# wesleyremote.net
KiCad netlist of a schematic drawn in EAGLE
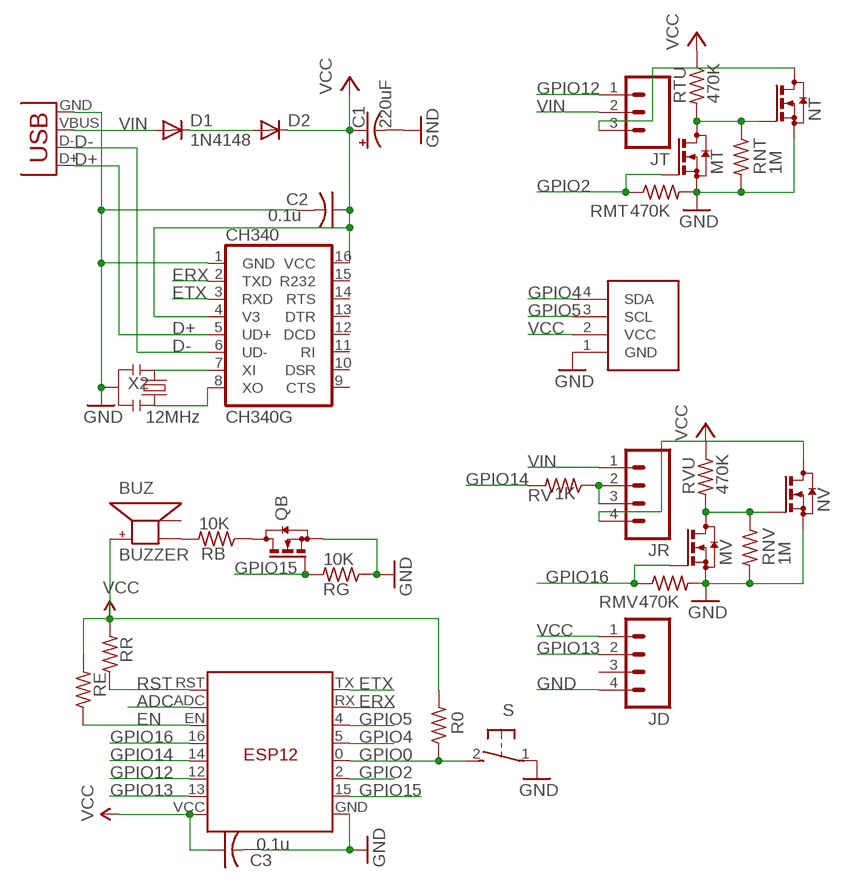
[diagram p0: schematic, sheet 1]

(export (version "E")
  (design (tool "Eeschema 10.0.6"))
  (components
    (comp (ref "BUZ")
      (value "BUZZER")
      (footprint "eagle-import:SMT-8585-BUZZER")
      (libsource (lib "eagle-import") (part "BUZZER"))
    )
    (comp (ref "C1")
      (value "220uF")
      (footprint "eagle-import:EIA3528-KIT")
      (libsource (lib "eagle-import") (part "CAP_POL3528-KIT"))
    )
    (comp (ref "C2")
      (value "0.1u")
      (footprint "eagle-import:C0603K")
      (libsource (lib "eagle-import") (part "C-USC0603K"))
    )
    (comp (ref "C3")
      (value "0.1u")
      (footprint "eagle-import:C0603K")
      (libsource (lib "eagle-import") (part "C-USC0603K"))
    )
    (comp (ref "CH340")
      (value "CH340G")
      (footprint "eagle-import:SO16")
      (libsource (lib "eagle-import") (part "CH340G"))
    )
    (comp (ref "D1")
      (value "1N4148")
      (footprint "eagle-import:MINIMELF")
      (libsource (lib "eagle-import") (part "DIODE-MINIMELF"))
    )
    (comp (ref "D2")
      (value "DIODE-MINIMELF")
      (footprint "eagle-import:MINIMELF")
      (libsource (lib "eagle-import") (part "DIODE-MINIMELF"))
    )
    (comp (ref "ESP12")
      (value "ESP12ESPWES")
      (footprint "eagle-import:ESP12_WES")
      (libsource (lib "eagle-import") (part "ESP12ESPWES"))
    )
    (comp (ref "JD")
      (value "M04DHT")
      (footprint "eagle-import:1X04_DHT_RFRX")
      (libsource (lib "eagle-import") (part "M04DHT"))
    )
    (comp (ref "JR")
      (value "M04RFRX")
      (footprint "eagle-import:1X04_RFRX")
      (libsource (lib "eagle-import") (part "M04RFRX"))
    )
    (comp (ref "JT")
      (value "M03RFTX")
      (footprint "eagle-import:1X03_RFTX")
      (libsource (lib "eagle-import") (part "M03RFTX"))
    )
    (comp (ref "MT")
      (value "AO3400")
      (footprint "eagle-import:SOT23")
      (libsource (lib "eagle-import") (part "BSS123"))
    )
    (comp (ref "MV")
      (value "AO3400")
      (footprint "eagle-import:SOT23")
      (libsource (lib "eagle-import") (part "BSS123"))
    )
    (comp (ref "NT")
      (value "AO3400")
      (footprint "eagle-import:SOT23")
      (libsource (lib "eagle-import") (part "BSS123"))
    )
    (comp (ref "NV")
      (value "AO3400")
      (footprint "eagle-import:SOT23")
      (libsource (lib "eagle-import") (part "BSS123"))
    )
    (comp (ref "QB")
      (value "AO3400")
      (footprint "eagle-import:SOT23")
      (libsource (lib "eagle-import") (part "BSS123"))
    )
    (comp (ref "R0")
      (value "R-US_R0603")
      (footprint "eagle-import:R0603")
      (libsource (lib "eagle-import") (part "R-US_R0603"))
    )
    (comp (ref "RB")
      (value "10K")
      (footprint "eagle-import:R0603")
      (libsource (lib "eagle-import") (part "adafruit2013_R-US_R0603"))
    )
    (comp (ref "RE")
      (value "R-US_R0603")
      (footprint "eagle-import:R0603")
      (libsource (lib "eagle-import") (part "R-US_R0603"))
    )
    (comp (ref "RG")
      (value "10K")
      (footprint "eagle-import:R0603")
      (libsource (lib "eagle-import") (part "adafruit2013_R-US_R0603"))
    )
    (comp (ref "RMT")
      (value "470K")
      (footprint "eagle-import:R0603")
      (libsource (lib "eagle-import") (part "R-US_R0603"))
    )
    (comp (ref "RMV")
      (value "470K")
      (footprint "eagle-import:R0603")
      (libsource (lib "eagle-import") (part "R-US_R0603"))
    )
    (comp (ref "RNT")
      (value "1M")
      (footprint "eagle-import:R0603")
      (libsource (lib "eagle-import") (part "R-US_R0603"))
    )
    (comp (ref "RNV")
      (value "1M")
      (footprint "eagle-import:R0603")
      (libsource (lib "eagle-import") (part "R-US_R0603"))
    )
    (comp (ref "RR")
      (value "R-US_R0603")
      (footprint "eagle-import:R0603")
      (libsource (lib "eagle-import") (part "R-US_R0603"))
    )
    (comp (ref "RTU")
      (value "470K")
      (footprint "eagle-import:R0603")
      (libsource (lib "eagle-import") (part "R-US_R0603"))
    )
    (comp (ref "RV")
      (value "1K")
      (footprint "eagle-import:R0603")
      (libsource (lib "eagle-import") (part "R-US_R0603"))
    )
    (comp (ref "RVU")
      (value "470K")
      (footprint "eagle-import:R0603")
      (libsource (lib "eagle-import") (part "R-US_R0603"))
    )
    (comp (ref "S")
      (value "31-XX")
      (footprint "eagle-import:B3F-31XX")
      (libsource (lib "eagle-import") (part "31-XX"))
    )
    (comp (ref "U$1")
      (value "SSD1306_OLED_I2C")
      (footprint "eagle-import:SSD1306_OLED_I2C")
      (libsource (lib "eagle-import") (part "SSD1306_OLED_I2C"))
    )
    (comp (ref "X2")
      (value "12MHz")
      (footprint "eagle-import:RESONATOR-SMD")
      (libsource (lib "eagle-import") (part "RESONATORSMD"))
    )
    (comp (ref "X3")
      (value "USBMICROB2")
      (footprint "eagle-import:USB-MICROB2")
      (libsource (lib "eagle-import") (part "USBMICROB2"))
    )
  )
  (nets
    (net (code "1") (name "/ADC") (class "Default")
      (node (ref "ESP12") (pin "ADC") (pinfunction "ADC_ADC") (pintype "bidirectional"))
    )
    (net (code "2") (name "/D+") (class "Default")
      (node (ref "CH340") (pin "5") (pinfunction "UD+_5") (pintype "bidirectional"))
      (node (ref "X3") (pin "D+") (pinfunction "D+_D+") (pintype "bidirectional"))
    )
    (net (code "3") (name "/D-") (class "Default")
      (node (ref "CH340") (pin "6") (pinfunction "UD-_6") (pintype "bidirectional"))
      (node (ref "X3") (pin "D-") (pinfunction "D-_D-") (pintype "bidirectional"))
    )
    (net (code "4") (name "/EN") (class "Default")
      (node (ref "ESP12") (pin "EN") (pinfunction "EN_EN") (pintype "bidirectional"))
      (node (ref "RE") (pin "1") (pinfunction "1_1") (pintype "passive"))
    )
    (net (code "5") (name "/ERX") (class "Default")
      (node (ref "CH340") (pin "2") (pinfunction "TXD_2") (pintype "bidirectional"))
      (node (ref "ESP12") (pin "RX") (pinfunction "RX_RX") (pintype "bidirectional"))
    )
    (net (code "6") (name "/ETX") (class "Default")
      (node (ref "CH340") (pin "3") (pinfunction "RXD_3") (pintype "bidirectional"))
      (node (ref "ESP12") (pin "TX") (pinfunction "TX_TX") (pintype "bidirectional"))
    )
    (net (code "7") (name "/GPIO0") (class "Default")
      (node (ref "ESP12") (pin "0") (pinfunction "G0_0") (pintype "bidirectional"))
      (node (ref "R0") (pin "1") (pinfunction "1_1") (pintype "passive"))
      (node (ref "S") (pin "2") (pinfunction "S_2") (pintype "passive"))
    )
    (net (code "8") (name "/GPIO2") (class "Default")
      (node (ref "ESP12") (pin "2") (pinfunction "G2_2") (pintype "bidirectional"))
      (node (ref "MT") (pin "1") (pinfunction "G_1") (pintype "passive"))
      (node (ref "RMT") (pin "1") (pinfunction "1_1") (pintype "passive"))
    )
    (net (code "9") (name "/GPIO4") (class "Default")
      (node (ref "ESP12") (pin "5") (pinfunction "G5_5") (pintype "bidirectional"))
      (node (ref "U$1") (pin "4") (pinfunction "SDA_4") (pintype "bidirectional"))
    )
    (net (code "10") (name "/GPIO5") (class "Default")
      (node (ref "ESP12") (pin "4") (pinfunction "G4_4") (pintype "bidirectional"))
      (node (ref "U$1") (pin "3") (pinfunction "SCL_3") (pintype "bidirectional"))
    )
    (net (code "11") (name "/GPIO12") (class "Default")
      (node (ref "ESP12") (pin "12") (pinfunction "G12_12") (pintype "bidirectional"))
      (node (ref "JT") (pin "1") (pinfunction "1_1") (pintype "passive"))
    )
    (net (code "12") (name "/GPIO13") (class "Default")
      (node (ref "ESP12") (pin "13") (pinfunction "G13_13") (pintype "bidirectional"))
      (node (ref "JD") (pin "2") (pinfunction "2_2") (pintype "passive"))
    )
    (net (code "13") (name "/GPIO14") (class "Default")
      (node (ref "ESP12") (pin "14") (pinfunction "G14_14") (pintype "bidirectional"))
      (node (ref "RV") (pin "2") (pinfunction "2_2") (pintype "passive"))
    )
    (net (code "14") (name "/GPIO15") (class "Default")
      (node (ref "ESP12") (pin "15") (pinfunction "G15_15") (pintype "bidirectional"))
      (node (ref "QB") (pin "1") (pinfunction "G_1") (pintype "passive"))
      (node (ref "RG") (pin "2") (pinfunction "2_2") (pintype "passive"))
    )
    (net (code "15") (name "/GPIO16") (class "Default")
      (node (ref "ESP12") (pin "16") (pinfunction "G16_16") (pintype "bidirectional"))
      (node (ref "MV") (pin "1") (pinfunction "G_1") (pintype "passive"))
      (node (ref "RMV") (pin "1") (pinfunction "1_1") (pintype "passive"))
    )
    (net (code "16") (name "/RST") (class "Default")
      (node (ref "ESP12") (pin "RST") (pinfunction "RST_RST") (pintype "bidirectional"))
      (node (ref "RR") (pin "1") (pinfunction "1_1") (pintype "passive"))
    )
    (net (code "17") (name "/VIN") (class "Default")
      (node (ref "D1") (pin "A") (pinfunction "A_A") (pintype "passive"))
      (node (ref "JR") (pin "1") (pinfunction "1_1") (pintype "passive"))
      (node (ref "JT") (pin "2") (pinfunction "2_2") (pintype "passive"))
      (node (ref "X3") (pin "VBUS") (pinfunction "VBUS_VBUS") (pintype "bidirectional"))
    )
    (net (code "18") (name "GND") (class "Default")
      (node (ref "C1") (pin "C") (pinfunction "-_C") (pintype "passive"))
      (node (ref "C2") (pin "2") (pinfunction "2_2") (pintype "passive"))
      (node (ref "C3") (pin "2") (pinfunction "2_2") (pintype "passive"))
      (node (ref "CH340") (pin "1") (pinfunction "GND_1") (pintype "power_in"))
      (node (ref "ESP12") (pin "GND") (pinfunction "GND_GND") (pintype "power_in"))
      (node (ref "JD") (pin "4") (pinfunction "4_4") (pintype "passive"))
      (node (ref "MT") (pin "2") (pinfunction "S_2") (pintype "passive"))
      (node (ref "MV") (pin "2") (pinfunction "S_2") (pintype "passive"))
      (node (ref "NT") (pin "2") (pinfunction "S_2") (pintype "passive"))
      (node (ref "NV") (pin "2") (pinfunction "S_2") (pintype "passive"))
      (node (ref "QB") (pin "2") (pinfunction "S_2") (pintype "passive"))
      (node (ref "RG") (pin "1") (pinfunction "1_1") (pintype "passive"))
      (node (ref "RMT") (pin "2") (pinfunction "2_2") (pintype "passive"))
      (node (ref "RMV") (pin "2") (pinfunction "2_2") (pintype "passive"))
      (node (ref "RNT") (pin "2") (pinfunction "2_2") (pintype "passive"))
      (node (ref "RNV") (pin "2") (pinfunction "2_2") (pintype "passive"))
      (node (ref "S") (pin "1") (pinfunction "P_1") (pintype "passive"))
      (node (ref "U$1") (pin "1") (pinfunction "GND_1") (pintype "power_in"))
      (node (ref "X2") (pin "2") (pinfunction "2_2") (pintype "passive"))
      (node (ref "X3") (pin "GND") (pinfunction "GND_GND") (pintype "bidirectional"))
    )
    (net (code "19") (name "Net-(BUZ-Pad-)") (class "Default")
      (node (ref "BUZ") (pin "-") (pinfunction "-_-") (pintype "passive"))
      (node (ref "RB") (pin "2") (pinfunction "2_2") (pintype "passive"))
    )
    (net (code "20") (name "Net-(CH340-XI)") (class "Default")
      (node (ref "CH340") (pin "7") (pinfunction "XI_7") (pintype "bidirectional"))
      (node (ref "X2") (pin "1") (pinfunction "1_1") (pintype "passive"))
    )
    (net (code "21") (name "Net-(CH340-XO)") (class "Default")
      (node (ref "CH340") (pin "8") (pinfunction "XO_8") (pintype "bidirectional"))
      (node (ref "X2") (pin "3") (pinfunction "3_3") (pintype "passive"))
    )
    (net (code "22") (name "Net-(D1-PadC)") (class "Default")
      (node (ref "D1") (pin "C") (pinfunction "C_C") (pintype "passive"))
      (node (ref "D2") (pin "A") (pinfunction "A_A") (pintype "passive"))
    )
    (net (code "23") (name "Net-(JR-Pad2)") (class "Default")
      (node (ref "JR") (pin "2") (pinfunction "2_2") (pintype "passive"))
      (node (ref "JR") (pin "3") (pinfunction "3_3") (pintype "passive"))
      (node (ref "RV") (pin "1") (pinfunction "1_1") (pintype "passive"))
    )
    (net (code "24") (name "Net-(MT-D)") (class "Default")
      (node (ref "MT") (pin "3") (pinfunction "D_3") (pintype "passive"))
      (node (ref "NT") (pin "1") (pinfunction "G_1") (pintype "passive"))
      (node (ref "RNT") (pin "1") (pinfunction "1_1") (pintype "passive"))
      (node (ref "RTU") (pin "2") (pinfunction "2_2") (pintype "passive"))
    )
    (net (code "25") (name "Net-(MV-D)") (class "Default")
      (node (ref "MV") (pin "3") (pinfunction "D_3") (pintype "passive"))
      (node (ref "NV") (pin "1") (pinfunction "G_1") (pintype "passive"))
      (node (ref "RNV") (pin "1") (pinfunction "1_1") (pintype "passive"))
      (node (ref "RVU") (pin "2") (pinfunction "2_2") (pintype "passive"))
    )
    (net (code "26") (name "Net-(NT-D)") (class "Default")
      (node (ref "JT") (pin "3") (pinfunction "3_3") (pintype "passive"))
      (node (ref "NT") (pin "3") (pinfunction "D_3") (pintype "passive"))
    )
    (net (code "27") (name "Net-(NV-D)") (class "Default")
      (node (ref "JR") (pin "4") (pinfunction "4_4") (pintype "passive"))
      (node (ref "NV") (pin "3") (pinfunction "D_3") (pintype "passive"))
    )
    (net (code "28") (name "Net-(QB-D)") (class "Default")
      (node (ref "QB") (pin "3") (pinfunction "D_3") (pintype "passive"))
      (node (ref "RB") (pin "1") (pinfunction "1_1") (pintype "passive"))
    )
    (net (code "29") (name "VCC") (class "Default")
      (node (ref "BUZ") (pin "+") (pinfunction "+_+") (pintype "passive"))
      (node (ref "C1") (pin "A") (pinfunction "+_A") (pintype "passive"))
      (node (ref "C2") (pin "1") (pinfunction "1_1") (pintype "passive"))
      (node (ref "C3") (pin "1") (pinfunction "1_1") (pintype "passive"))
      (node (ref "CH340") (pin "16") (pinfunction "VCC_16") (pintype "power_in"))
      (node (ref "CH340") (pin "4") (pinfunction "V3_4") (pintype "bidirectional"))
      (node (ref "D2") (pin "C") (pinfunction "C_C") (pintype "passive"))
      (node (ref "ESP12") (pin "VCC") (pinfunction "VCC_VCC") (pintype "power_in"))
      (node (ref "JD") (pin "1") (pinfunction "1_1") (pintype "passive"))
      (node (ref "R0") (pin "2") (pinfunction "2_2") (pintype "passive"))
      (node (ref "RE") (pin "2") (pinfunction "2_2") (pintype "passive"))
      (node (ref "RR") (pin "2") (pinfunction "2_2") (pintype "passive"))
      (node (ref "RTU") (pin "1") (pinfunction "1_1") (pintype "passive"))
      (node (ref "RVU") (pin "1") (pinfunction "1_1") (pintype "passive"))
      (node (ref "U$1") (pin "2") (pinfunction "VCC_2") (pintype "power_in"))
    )
    (net (code "30") (name "unconnected-(BUZ-PadA-)") (class "Default")
      (node (ref "BUZ") (pin "A-") (pinfunction "A-_A-") (pintype "passive"))
    )
    (net (code "31") (name "unconnected-(CH340-CTS-Pad9)") (class "Default")
      (node (ref "CH340") (pin "9") (pinfunction "CTS_9") (pintype "bidirectional"))
    )
    (net (code "32") (name "unconnected-(CH340-DCD-Pad12)") (class "Default")
      (node (ref "CH340") (pin "12") (pinfunction "DCD_12") (pintype "bidirectional"))
    )
    (net (code "33") (name "unconnected-(CH340-DSR-Pad10)") (class "Default")
      (node (ref "CH340") (pin "10") (pinfunction "DSR_10") (pintype "bidirectional"))
    )
    (net (code "34") (name "unconnected-(CH340-DTR-Pad13)") (class "Default")
      (node (ref "CH340") (pin "13") (pinfunction "DTR_13") (pintype "bidirectional"))
    )
    (net (code "35") (name "unconnected-(CH340-R232-Pad15)") (class "Default")
      (node (ref "CH340") (pin "15") (pinfunction "R232_15") (pintype "bidirectional"))
    )
    (net (code "36") (name "unconnected-(CH340-RI-Pad11)") (class "Default")
      (node (ref "CH340") (pin "11") (pinfunction "RI_11") (pintype "bidirectional"))
    )
    (net (code "37") (name "unconnected-(CH340-RTS-Pad14)") (class "Default")
      (node (ref "CH340") (pin "14") (pinfunction "RTS_14") (pintype "bidirectional"))
    )
    (net (code "38") (name "unconnected-(JD-Pad3)") (class "Default")
      (node (ref "JD") (pin "3") (pinfunction "3_3") (pintype "passive"))
    )
  )
)
